# Motor_Controller_Shield.net
KiCad netlist of a schematic drawn in EAGLE
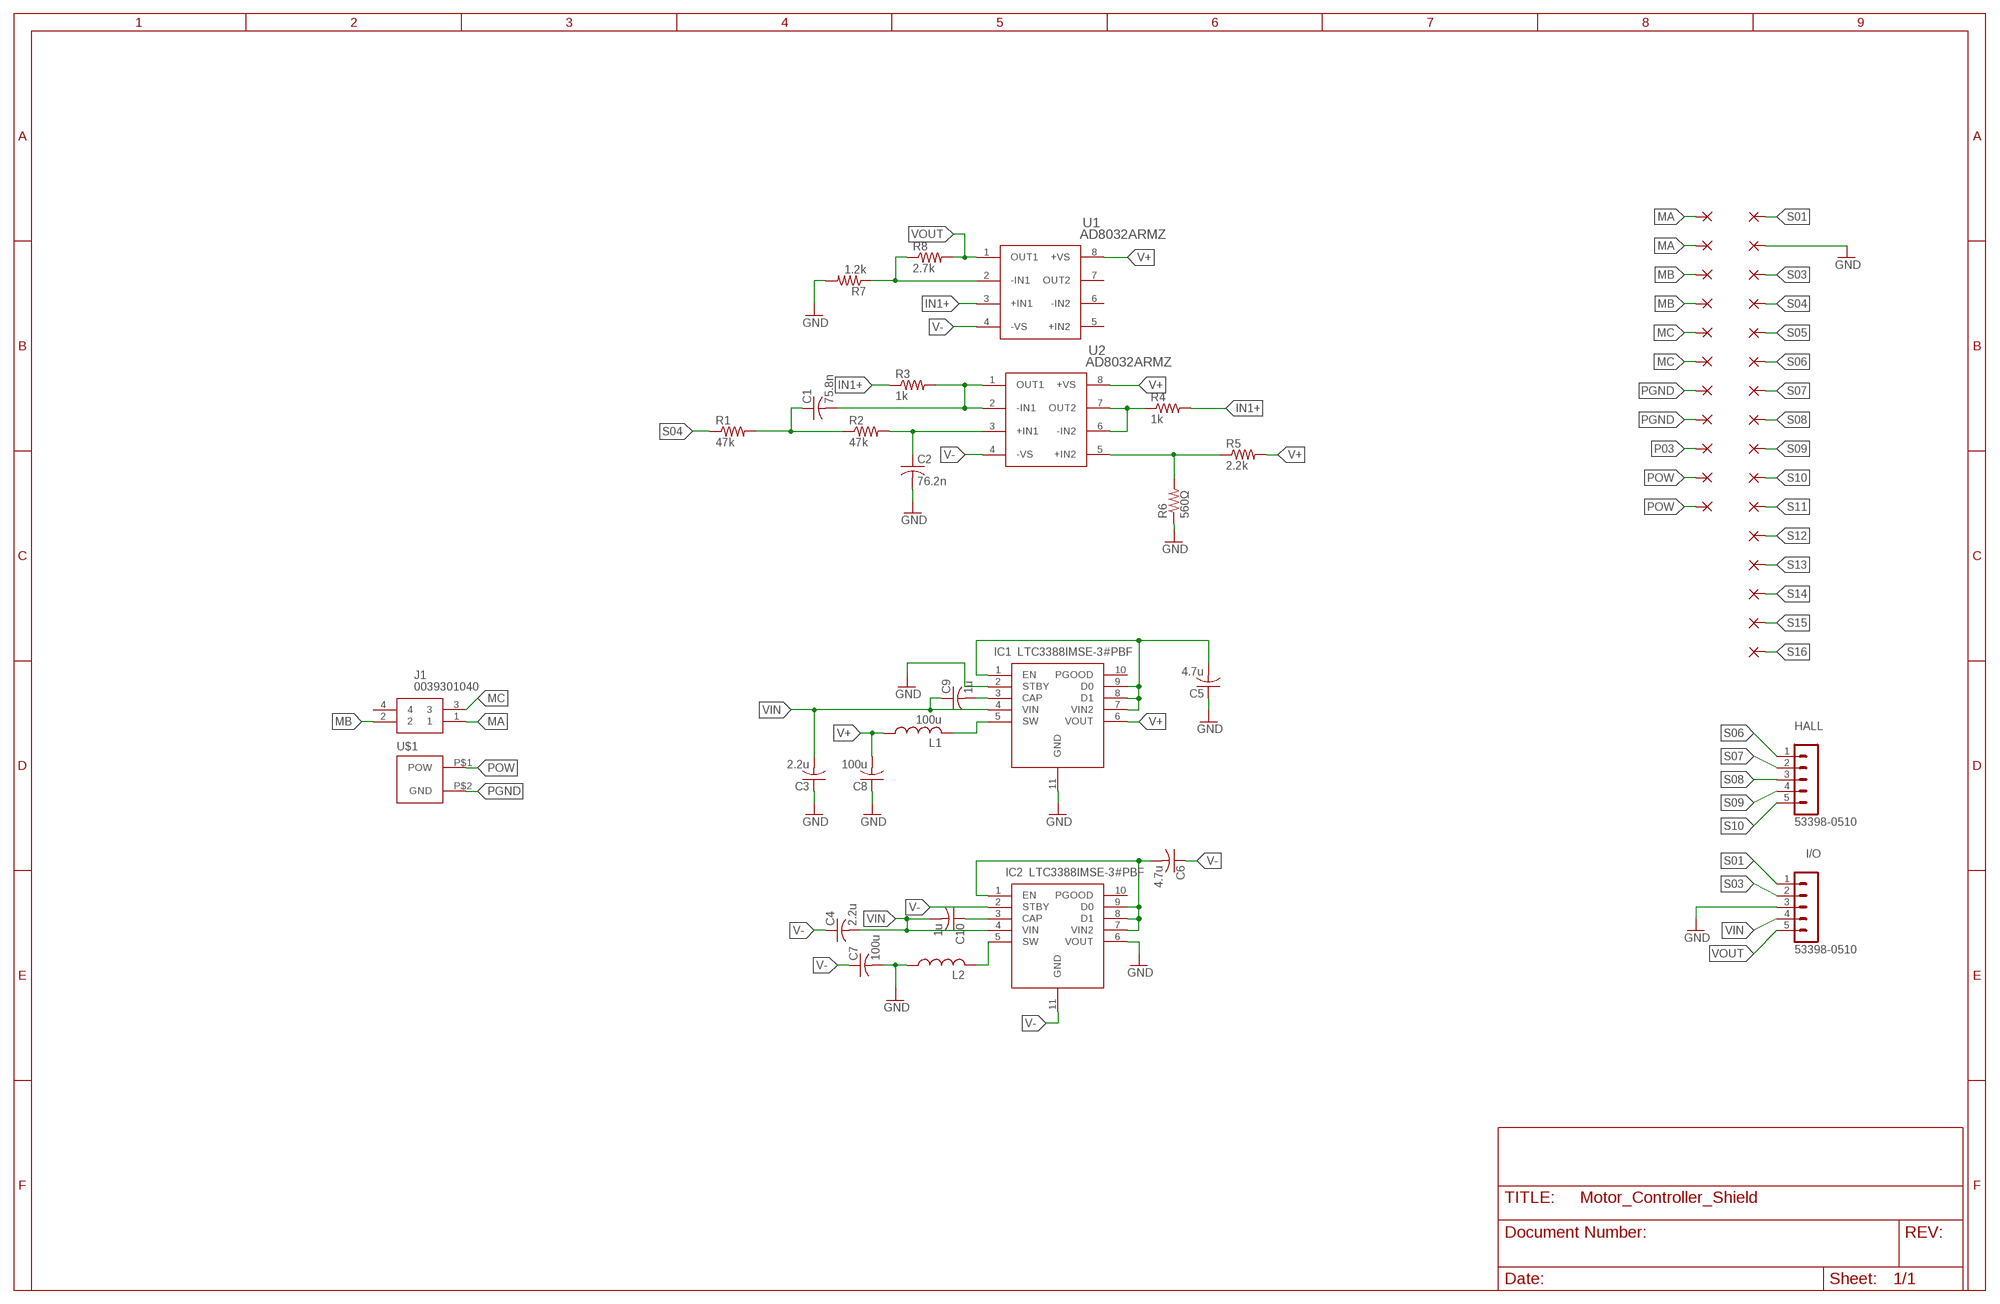
[diagram p0: schematic, sheet 1]

(export (version "E")
  (design (tool "Eeschema 10.0.6"))
  (components
    (comp (ref "C1")
      (value "75.8n")
      (footprint "eagle-import:C0805")
      (libsource (lib "eagle-import") (part "C-USC0805"))
    )
    (comp (ref "C2")
      (value "76.2n")
      (footprint "eagle-import:C0805")
      (libsource (lib "eagle-import") (part "C-USC0805"))
    )
    (comp (ref "C3")
      (value "2.2u")
      (footprint "eagle-import:C0805")
      (libsource (lib "eagle-import") (part "C-USC0805"))
    )
    (comp (ref "C4")
      (value "2.2u")
      (footprint "eagle-import:C0805")
      (libsource (lib "eagle-import") (part "C-USC0805"))
    )
    (comp (ref "C5")
      (value "4.7u")
      (footprint "eagle-import:C0805")
      (libsource (lib "eagle-import") (part "C-USC0805"))
    )
    (comp (ref "C6")
      (value "4.7u")
      (footprint "eagle-import:C0805")
      (libsource (lib "eagle-import") (part "C-USC0805"))
    )
    (comp (ref "C7")
      (value "100u")
      (footprint "eagle-import:C0805")
      (libsource (lib "eagle-import") (part "C-USC0805"))
    )
    (comp (ref "C8")
      (value "100u")
      (footprint "eagle-import:C0805")
      (libsource (lib "eagle-import") (part "C-USC0805"))
    )
    (comp (ref "C9")
      (value "1u")
      (footprint "eagle-import:C0805")
      (libsource (lib "eagle-import") (part "C-USC0805"))
    )
    (comp (ref "C10")
      (value "1u")
      (footprint "eagle-import:C0805")
      (libsource (lib "eagle-import") (part "C-USC0805"))
    )
    (comp (ref "HALL")
      (value "53398-0510")
      (footprint "eagle-import:53398-0510")
      (libsource (lib "eagle-import") (part "53398-0510"))
    )
    (comp (ref "I/O")
      (value "53398-0510")
      (footprint "eagle-import:53398-0510")
      (libsource (lib "eagle-import") (part "53398-0510"))
    )
    (comp (ref "IC1")
      (value "LTC3388IMSE-3#PBF")
      (footprint "eagle-import:SOP50P490X110-11N")
      (fields (field (name "MOUSER_PART_NUMBER") "584-LTC3388IMSE-3PBF"))
      (libsource (lib "eagle-import") (part "LTC3388IMSE-3#PBF"))
    )
    (comp (ref "IC2")
      (value "LTC3388IMSE-3#PBF")
      (footprint "eagle-import:SOP50P490X110-11N")
      (fields (field (name "MOUSER_PART_NUMBER") "584-LTC3388IMSE-3PBF"))
      (libsource (lib "eagle-import") (part "LTC3388IMSE-3#PBF"))
    )
    (comp (ref "J1")
      (value "0039301040")
      (footprint "eagle-import:0039301040")
      (libsource (lib "eagle-import") (part "0039301040"))
    )
    (comp (ref "L1")
      (value "100u")
      (footprint "eagle-import:L2012C")
      (libsource (lib "eagle-import") (part "L-USL2012C"))
    )
    (comp (ref "L2")
      (value "L-USL2012C")
      (footprint "eagle-import:L2012C")
      (libsource (lib "eagle-import") (part "L-USL2012C"))
    )
    (comp (ref "P01")
      (value "1,6/0,9")
      (footprint "eagle-import:1,6_0,9")
      (libsource (lib "eagle-import") (part "1,6/0,9"))
    )
    (comp (ref "P02")
      (value "1,6/0,9")
      (footprint "eagle-import:1,6_0,9")
      (libsource (lib "eagle-import") (part "1,6/0,9"))
    )
    (comp (ref "P03")
      (value "1,6/0,9")
      (footprint "eagle-import:1,6_0,9")
      (libsource (lib "eagle-import") (part "1,6/0,9"))
    )
    (comp (ref "P04")
      (value "1,6/0,9")
      (footprint "eagle-import:1,6_0,9")
      (libsource (lib "eagle-import") (part "1,6/0,9"))
    )
    (comp (ref "P05")
      (value "1,6/0,9")
      (footprint "eagle-import:1,6_0,9")
      (libsource (lib "eagle-import") (part "1,6/0,9"))
    )
    (comp (ref "P06")
      (value "1,6/0,9")
      (footprint "eagle-import:1,6_0,9")
      (libsource (lib "eagle-import") (part "1,6/0,9"))
    )
    (comp (ref "P07")
      (value "1,6/0,9")
      (footprint "eagle-import:1,6_0,9")
      (libsource (lib "eagle-import") (part "1,6/0,9"))
    )
    (comp (ref "P08")
      (value "1,6/0,9")
      (footprint "eagle-import:1,6_0,9")
      (libsource (lib "eagle-import") (part "1,6/0,9"))
    )
    (comp (ref "P09")
      (value "1,6/0,9")
      (footprint "eagle-import:1,6_0,9")
      (libsource (lib "eagle-import") (part "1,6/0,9"))
    )
    (comp (ref "P10")
      (value "1,6/0,9")
      (footprint "eagle-import:1,6_0,9")
      (libsource (lib "eagle-import") (part "1,6/0,9"))
    )
    (comp (ref "P11")
      (value "1,6/0,9")
      (footprint "eagle-import:1,6_0,9")
      (libsource (lib "eagle-import") (part "1,6/0,9"))
    )
    (comp (ref "R1")
      (value "47k")
      (footprint "eagle-import:R0805")
      (libsource (lib "eagle-import") (part "R-US_R0805"))
    )
    (comp (ref "R2")
      (value "47k")
      (footprint "eagle-import:R0805")
      (libsource (lib "eagle-import") (part "R-US_R0805"))
    )
    (comp (ref "R3")
      (value "1k")
      (footprint "eagle-import:R0805")
      (libsource (lib "eagle-import") (part "R-US_R0805"))
    )
    (comp (ref "R4")
      (value "1k")
      (footprint "eagle-import:R0805")
      (libsource (lib "eagle-import") (part "R-US_R0805"))
    )
    (comp (ref "R5")
      (value "2.2k")
      (footprint "eagle-import:R0805")
      (libsource (lib "eagle-import") (part "R-US_R0805"))
    )
    (comp (ref "R6")
      (value "560Ω")
      (footprint "eagle-import:R0805")
      (libsource (lib "eagle-import") (part "R-US_R0805"))
    )
    (comp (ref "R7")
      (value "1.2k")
      (footprint "eagle-import:R0805")
      (libsource (lib "eagle-import") (part "R-US_R0805"))
    )
    (comp (ref "R8")
      (value "2.7k")
      (footprint "eagle-import:R0805")
      (libsource (lib "eagle-import") (part "R-US_R0805"))
    )
    (comp (ref "S01")
      (value "1,6/0,9")
      (footprint "eagle-import:1,6_0,9")
      (libsource (lib "eagle-import") (part "1,6/0,9"))
    )
    (comp (ref "S02")
      (value "1,6/0,9")
      (footprint "eagle-import:1,6_0,9")
      (libsource (lib "eagle-import") (part "1,6/0,9"))
    )
    (comp (ref "S03")
      (value "1,6/0,9")
      (footprint "eagle-import:1,6_0,9")
      (libsource (lib "eagle-import") (part "1,6/0,9"))
    )
    (comp (ref "S04")
      (value "1,6/0,9")
      (footprint "eagle-import:1,6_0,9")
      (libsource (lib "eagle-import") (part "1,6/0,9"))
    )
    (comp (ref "S05")
      (value "1,6/0,9")
      (footprint "eagle-import:1,6_0,9")
      (libsource (lib "eagle-import") (part "1,6/0,9"))
    )
    (comp (ref "S06")
      (value "1,6/0,9")
      (footprint "eagle-import:1,6_0,9")
      (libsource (lib "eagle-import") (part "1,6/0,9"))
    )
    (comp (ref "S07")
      (value "1,6/0,9")
      (footprint "eagle-import:1,6_0,9")
      (libsource (lib "eagle-import") (part "1,6/0,9"))
    )
    (comp (ref "S08")
      (value "1,6/0,9")
      (footprint "eagle-import:1,6_0,9")
      (libsource (lib "eagle-import") (part "1,6/0,9"))
    )
    (comp (ref "S09")
      (value "1,6/0,9")
      (footprint "eagle-import:1,6_0,9")
      (libsource (lib "eagle-import") (part "1,6/0,9"))
    )
    (comp (ref "S10")
      (value "1,6/0,9")
      (footprint "eagle-import:1,6_0,9")
      (libsource (lib "eagle-import") (part "1,6/0,9"))
    )
    (comp (ref "S11")
      (value "1,6/0,9")
      (footprint "eagle-import:1,6_0,9")
      (libsource (lib "eagle-import") (part "1,6/0,9"))
    )
    (comp (ref "S12")
      (value "1,6/0,9")
      (footprint "eagle-import:1,6_0,9")
      (libsource (lib "eagle-import") (part "1,6/0,9"))
    )
    (comp (ref "S13")
      (value "1,6/0,9")
      (footprint "eagle-import:1,6_0,9")
      (libsource (lib "eagle-import") (part "1,6/0,9"))
    )
    (comp (ref "S14")
      (value "1,6/0,9")
      (footprint "eagle-import:1,6_0,9")
      (libsource (lib "eagle-import") (part "1,6/0,9"))
    )
    (comp (ref "S15")
      (value "1,6/0,9")
      (footprint "eagle-import:1,6_0,9")
      (libsource (lib "eagle-import") (part "1,6/0,9"))
    )
    (comp (ref "S16")
      (value "1,6/0,9")
      (footprint "eagle-import:1,6_0,9")
      (libsource (lib "eagle-import") (part "1,6/0,9"))
    )
    (comp (ref "U$1")
      (value "JR_2PM_DEV")
      (footprint "eagle-import:JR_2PM_B_FP")
      (libsource (lib "eagle-import") (part "JR_2PM_DEV"))
    )
    (comp (ref "U1")
      (value "AD8032ARMZ")
      (footprint "eagle-import:RM_8")
      (libsource (lib "eagle-import") (part "AD8032ARMZ"))
    )
    (comp (ref "U2")
      (value "AD8032ARMZ")
      (footprint "eagle-import:RM_8")
      (libsource (lib "eagle-import") (part "AD8032ARMZ"))
    )
  )
  (nets
    (net (code "1") (name "GND") (class "Default")
      (node (ref "C2") (pin "2") (pinfunction "2_2") (pintype "passive"))
      (node (ref "C3") (pin "1") (pinfunction "1_1") (pintype "passive"))
      (node (ref "C5") (pin "1") (pinfunction "1_1") (pintype "passive"))
      (node (ref "C7") (pin "2") (pinfunction "2_2") (pintype "passive"))
      (node (ref "C8") (pin "1") (pinfunction "1_1") (pintype "passive"))
      (node (ref "I/O") (pin "3") (pinfunction "3_3") (pintype "passive"))
      (node (ref "IC1") (pin "11") (pinfunction "GND_11") (pintype "bidirectional"))
      (node (ref "IC1") (pin "2") (pinfunction "STBY_2") (pintype "bidirectional"))
      (node (ref "IC2") (pin "6") (pinfunction "VOUT_6") (pintype "bidirectional"))
      (node (ref "L2") (pin "1") (pinfunction "1_1") (pintype "passive"))
      (node (ref "R6") (pin "1") (pinfunction "1_1") (pintype "passive"))
      (node (ref "R7") (pin "2") (pinfunction "2_2") (pintype "passive"))
      (node (ref "S02") (pin "1") (pinfunction "P_1") (pintype "passive"))
    )
    (net (code "2") (name "IN1+") (class "Default")
      (node (ref "R3") (pin "1") (pinfunction "1_1") (pintype "passive"))
      (node (ref "R4") (pin "2") (pinfunction "2_2") (pintype "passive"))
      (node (ref "U1") (pin "3") (pinfunction "+IN1_3") (pintype "passive"))
    )
    (net (code "3") (name "MA") (class "Default")
      (node (ref "J1") (pin "1") (pinfunction "1_1") (pintype "bidirectional"))
      (node (ref "P01") (pin "1") (pinfunction "P_1") (pintype "passive"))
      (node (ref "P02") (pin "1") (pinfunction "P_1") (pintype "passive"))
    )
    (net (code "4") (name "MB") (class "Default")
      (node (ref "J1") (pin "2") (pinfunction "2_2") (pintype "bidirectional"))
      (node (ref "P03") (pin "1") (pinfunction "P_1") (pintype "passive"))
      (node (ref "P04") (pin "1") (pinfunction "P_1") (pintype "passive"))
    )
    (net (code "5") (name "MC") (class "Default")
      (node (ref "J1") (pin "3") (pinfunction "3_3") (pintype "bidirectional"))
      (node (ref "P05") (pin "1") (pinfunction "P_1") (pintype "passive"))
      (node (ref "P06") (pin "1") (pinfunction "P_1") (pintype "passive"))
    )
    (net (code "6") (name "Net-(C1-Pad1)") (class "Default")
      (node (ref "C1") (pin "1") (pinfunction "1_1") (pintype "passive"))
      (node (ref "R1") (pin "2") (pinfunction "2_2") (pintype "passive"))
      (node (ref "R2") (pin "1") (pinfunction "1_1") (pintype "passive"))
    )
    (net (code "7") (name "Net-(IC1-CAP)") (class "Default")
      (node (ref "C9") (pin "2") (pinfunction "2_2") (pintype "passive"))
      (node (ref "IC1") (pin "3") (pinfunction "CAP_3") (pintype "bidirectional"))
    )
    (net (code "8") (name "Net-(IC1-D0)") (class "Default")
      (node (ref "C5") (pin "2") (pinfunction "2_2") (pintype "passive"))
      (node (ref "IC1") (pin "1") (pinfunction "EN_1") (pintype "bidirectional"))
      (node (ref "IC1") (pin "7") (pinfunction "VIN2_7") (pintype "bidirectional"))
      (node (ref "IC1") (pin "8") (pinfunction "D1_8") (pintype "bidirectional"))
      (node (ref "IC1") (pin "9") (pinfunction "D0_9") (pintype "bidirectional"))
    )
    (net (code "9") (name "Net-(IC1-SW)") (class "Default")
      (node (ref "IC1") (pin "5") (pinfunction "SW_5") (pintype "bidirectional"))
      (node (ref "L1") (pin "2") (pinfunction "2_2") (pintype "passive"))
    )
    (net (code "10") (name "Net-(IC2-CAP)") (class "Default")
      (node (ref "C10") (pin "1") (pinfunction "1_1") (pintype "passive"))
      (node (ref "IC2") (pin "3") (pinfunction "CAP_3") (pintype "bidirectional"))
    )
    (net (code "11") (name "Net-(IC2-D0)") (class "Default")
      (node (ref "C6") (pin "2") (pinfunction "2_2") (pintype "passive"))
      (node (ref "IC2") (pin "1") (pinfunction "EN_1") (pintype "bidirectional"))
      (node (ref "IC2") (pin "7") (pinfunction "VIN2_7") (pintype "bidirectional"))
      (node (ref "IC2") (pin "8") (pinfunction "D1_8") (pintype "bidirectional"))
      (node (ref "IC2") (pin "9") (pinfunction "D0_9") (pintype "bidirectional"))
    )
    (net (code "12") (name "Net-(IC2-SW)") (class "Default")
      (node (ref "IC2") (pin "5") (pinfunction "SW_5") (pintype "bidirectional"))
      (node (ref "L2") (pin "2") (pinfunction "2_2") (pintype "passive"))
    )
    (net (code "13") (name "Net-(U1--IN1)") (class "Default")
      (node (ref "R7") (pin "1") (pinfunction "1_1") (pintype "passive"))
      (node (ref "R8") (pin "1") (pinfunction "1_1") (pintype "passive"))
      (node (ref "U1") (pin "2") (pinfunction "-IN1_2") (pintype "passive"))
    )
    (net (code "14") (name "Net-(U2-+IN1)") (class "Default")
      (node (ref "C2") (pin "1") (pinfunction "1_1") (pintype "passive"))
      (node (ref "R2") (pin "2") (pinfunction "2_2") (pintype "passive"))
      (node (ref "U2") (pin "3") (pinfunction "+IN1_3") (pintype "passive"))
    )
    (net (code "15") (name "Net-(U2-+IN2)") (class "Default")
      (node (ref "R5") (pin "1") (pinfunction "1_1") (pintype "passive"))
      (node (ref "R6") (pin "2") (pinfunction "2_2") (pintype "passive"))
      (node (ref "U2") (pin "5") (pinfunction "+IN2_5") (pintype "passive"))
    )
    (net (code "16") (name "Net-(U2--IN1)") (class "Default")
      (node (ref "C1") (pin "2") (pinfunction "2_2") (pintype "passive"))
      (node (ref "R3") (pin "2") (pinfunction "2_2") (pintype "passive"))
      (node (ref "U2") (pin "1") (pinfunction "OUT1_1") (pintype "passive"))
      (node (ref "U2") (pin "2") (pinfunction "-IN1_2") (pintype "passive"))
    )
    (net (code "17") (name "Net-(U2--IN2)") (class "Default")
      (node (ref "R4") (pin "1") (pinfunction "1_1") (pintype "passive"))
      (node (ref "U2") (pin "6") (pinfunction "-IN2_6") (pintype "passive"))
      (node (ref "U2") (pin "7") (pinfunction "OUT2_7") (pintype "passive"))
    )
    (net (code "18") (name "P03") (class "Default")
      (node (ref "P09") (pin "1") (pinfunction "P_1") (pintype "passive"))
    )
    (net (code "19") (name "PGND") (class "Default")
      (node (ref "P07") (pin "1") (pinfunction "P_1") (pintype "passive"))
      (node (ref "P08") (pin "1") (pinfunction "P_1") (pintype "passive"))
      (node (ref "U$1") (pin "P$2") (pinfunction "GND_P$2") (pintype "bidirectional"))
    )
    (net (code "20") (name "POW") (class "Default")
      (node (ref "P10") (pin "1") (pinfunction "P_1") (pintype "passive"))
      (node (ref "P11") (pin "1") (pinfunction "P_1") (pintype "passive"))
      (node (ref "U$1") (pin "P$1") (pinfunction "POW_P$1") (pintype "bidirectional"))
    )
    (net (code "21") (name "S01") (class "Default")
      (node (ref "I/O") (pin "1") (pinfunction "1_1") (pintype "passive"))
      (node (ref "S01") (pin "1") (pinfunction "P_1") (pintype "passive"))
    )
    (net (code "22") (name "S03") (class "Default")
      (node (ref "I/O") (pin "2") (pinfunction "2_2") (pintype "passive"))
      (node (ref "S03") (pin "1") (pinfunction "P_1") (pintype "passive"))
    )
    (net (code "23") (name "S04") (class "Default")
      (node (ref "R1") (pin "1") (pinfunction "1_1") (pintype "passive"))
      (node (ref "S04") (pin "1") (pinfunction "P_1") (pintype "passive"))
    )
    (net (code "24") (name "S05") (class "Default")
      (node (ref "S05") (pin "1") (pinfunction "P_1") (pintype "passive"))
    )
    (net (code "25") (name "S06") (class "Default")
      (node (ref "HALL") (pin "1") (pinfunction "1_1") (pintype "passive"))
      (node (ref "S06") (pin "1") (pinfunction "P_1") (pintype "passive"))
    )
    (net (code "26") (name "S07") (class "Default")
      (node (ref "HALL") (pin "2") (pinfunction "2_2") (pintype "passive"))
      (node (ref "S07") (pin "1") (pinfunction "P_1") (pintype "passive"))
    )
    (net (code "27") (name "S08") (class "Default")
      (node (ref "HALL") (pin "3") (pinfunction "3_3") (pintype "passive"))
      (node (ref "S08") (pin "1") (pinfunction "P_1") (pintype "passive"))
    )
    (net (code "28") (name "S09") (class "Default")
      (node (ref "HALL") (pin "4") (pinfunction "4_4") (pintype "passive"))
      (node (ref "S09") (pin "1") (pinfunction "P_1") (pintype "passive"))
    )
    (net (code "29") (name "S10") (class "Default")
      (node (ref "HALL") (pin "5") (pinfunction "5_5") (pintype "passive"))
      (node (ref "S10") (pin "1") (pinfunction "P_1") (pintype "passive"))
    )
    (net (code "30") (name "S11") (class "Default")
      (node (ref "S11") (pin "1") (pinfunction "P_1") (pintype "passive"))
    )
    (net (code "31") (name "S12") (class "Default")
      (node (ref "S12") (pin "1") (pinfunction "P_1") (pintype "passive"))
    )
    (net (code "32") (name "S13") (class "Default")
      (node (ref "S13") (pin "1") (pinfunction "P_1") (pintype "passive"))
    )
    (net (code "33") (name "S14") (class "Default")
      (node (ref "S14") (pin "1") (pinfunction "P_1") (pintype "passive"))
    )
    (net (code "34") (name "S15") (class "Default")
      (node (ref "S15") (pin "1") (pinfunction "P_1") (pintype "passive"))
    )
    (net (code "35") (name "S16") (class "Default")
      (node (ref "S16") (pin "1") (pinfunction "P_1") (pintype "passive"))
    )
    (net (code "36") (name "V+") (class "Default")
      (node (ref "C8") (pin "2") (pinfunction "2_2") (pintype "passive"))
      (node (ref "IC1") (pin "6") (pinfunction "VOUT_6") (pintype "bidirectional"))
      (node (ref "L1") (pin "1") (pinfunction "1_1") (pintype "passive"))
      (node (ref "R5") (pin "2") (pinfunction "2_2") (pintype "passive"))
      (node (ref "U1") (pin "8") (pinfunction "+VS_8") (pintype "power_in"))
      (node (ref "U2") (pin "8") (pinfunction "+VS_8") (pintype "power_in"))
    )
    (net (code "37") (name "V-") (class "Default")
      (node (ref "C4") (pin "1") (pinfunction "1_1") (pintype "passive"))
      (node (ref "C6") (pin "1") (pinfunction "1_1") (pintype "passive"))
      (node (ref "C7") (pin "1") (pinfunction "1_1") (pintype "passive"))
      (node (ref "IC2") (pin "11") (pinfunction "GND_11") (pintype "bidirectional"))
      (node (ref "IC2") (pin "2") (pinfunction "STBY_2") (pintype "bidirectional"))
      (node (ref "U1") (pin "4") (pinfunction "-VS_4") (pintype "power_in"))
      (node (ref "U2") (pin "4") (pinfunction "-VS_4") (pintype "power_in"))
    )
    (net (code "38") (name "VIN") (class "Default")
      (node (ref "C10") (pin "2") (pinfunction "2_2") (pintype "passive"))
      (node (ref "C3") (pin "2") (pinfunction "2_2") (pintype "passive"))
      (node (ref "C4") (pin "2") (pinfunction "2_2") (pintype "passive"))
      (node (ref "C9") (pin "1") (pinfunction "1_1") (pintype "passive"))
      (node (ref "I/O") (pin "4") (pinfunction "4_4") (pintype "passive"))
      (node (ref "IC1") (pin "4") (pinfunction "VIN_4") (pintype "bidirectional"))
      (node (ref "IC2") (pin "4") (pinfunction "VIN_4") (pintype "bidirectional"))
    )
    (net (code "39") (name "VOUT") (class "Default")
      (node (ref "I/O") (pin "5") (pinfunction "5_5") (pintype "passive"))
      (node (ref "R8") (pin "2") (pinfunction "2_2") (pintype "passive"))
      (node (ref "U1") (pin "1") (pinfunction "OUT1_1") (pintype "passive"))
    )
    (net (code "40") (name "unconnected-(IC1-PGOOD-Pad10)") (class "Default")
      (node (ref "IC1") (pin "10") (pinfunction "PGOOD_10") (pintype "bidirectional"))
    )
    (net (code "41") (name "unconnected-(IC2-PGOOD-Pad10)") (class "Default")
      (node (ref "IC2") (pin "10") (pinfunction "PGOOD_10") (pintype "bidirectional"))
    )
    (net (code "42") (name "unconnected-(J1-Pad4)") (class "Default")
      (node (ref "J1") (pin "4") (pinfunction "4_4") (pintype "bidirectional"))
    )
    (net (code "43") (name "unconnected-(U1-+IN2-Pad5)") (class "Default")
      (node (ref "U1") (pin "5") (pinfunction "+IN2_5") (pintype "passive"))
    )
    (net (code "44") (name "unconnected-(U1--IN2-Pad6)") (class "Default")
      (node (ref "U1") (pin "6") (pinfunction "-IN2_6") (pintype "passive"))
    )
    (net (code "45") (name "unconnected-(U1-OUT2-Pad7)") (class "Default")
      (node (ref "U1") (pin "7") (pinfunction "OUT2_7") (pintype "passive"))
    )
  )
)
